# ESC-simple_V1A.net
KiCad netlist of a schematic drawn in EAGLE
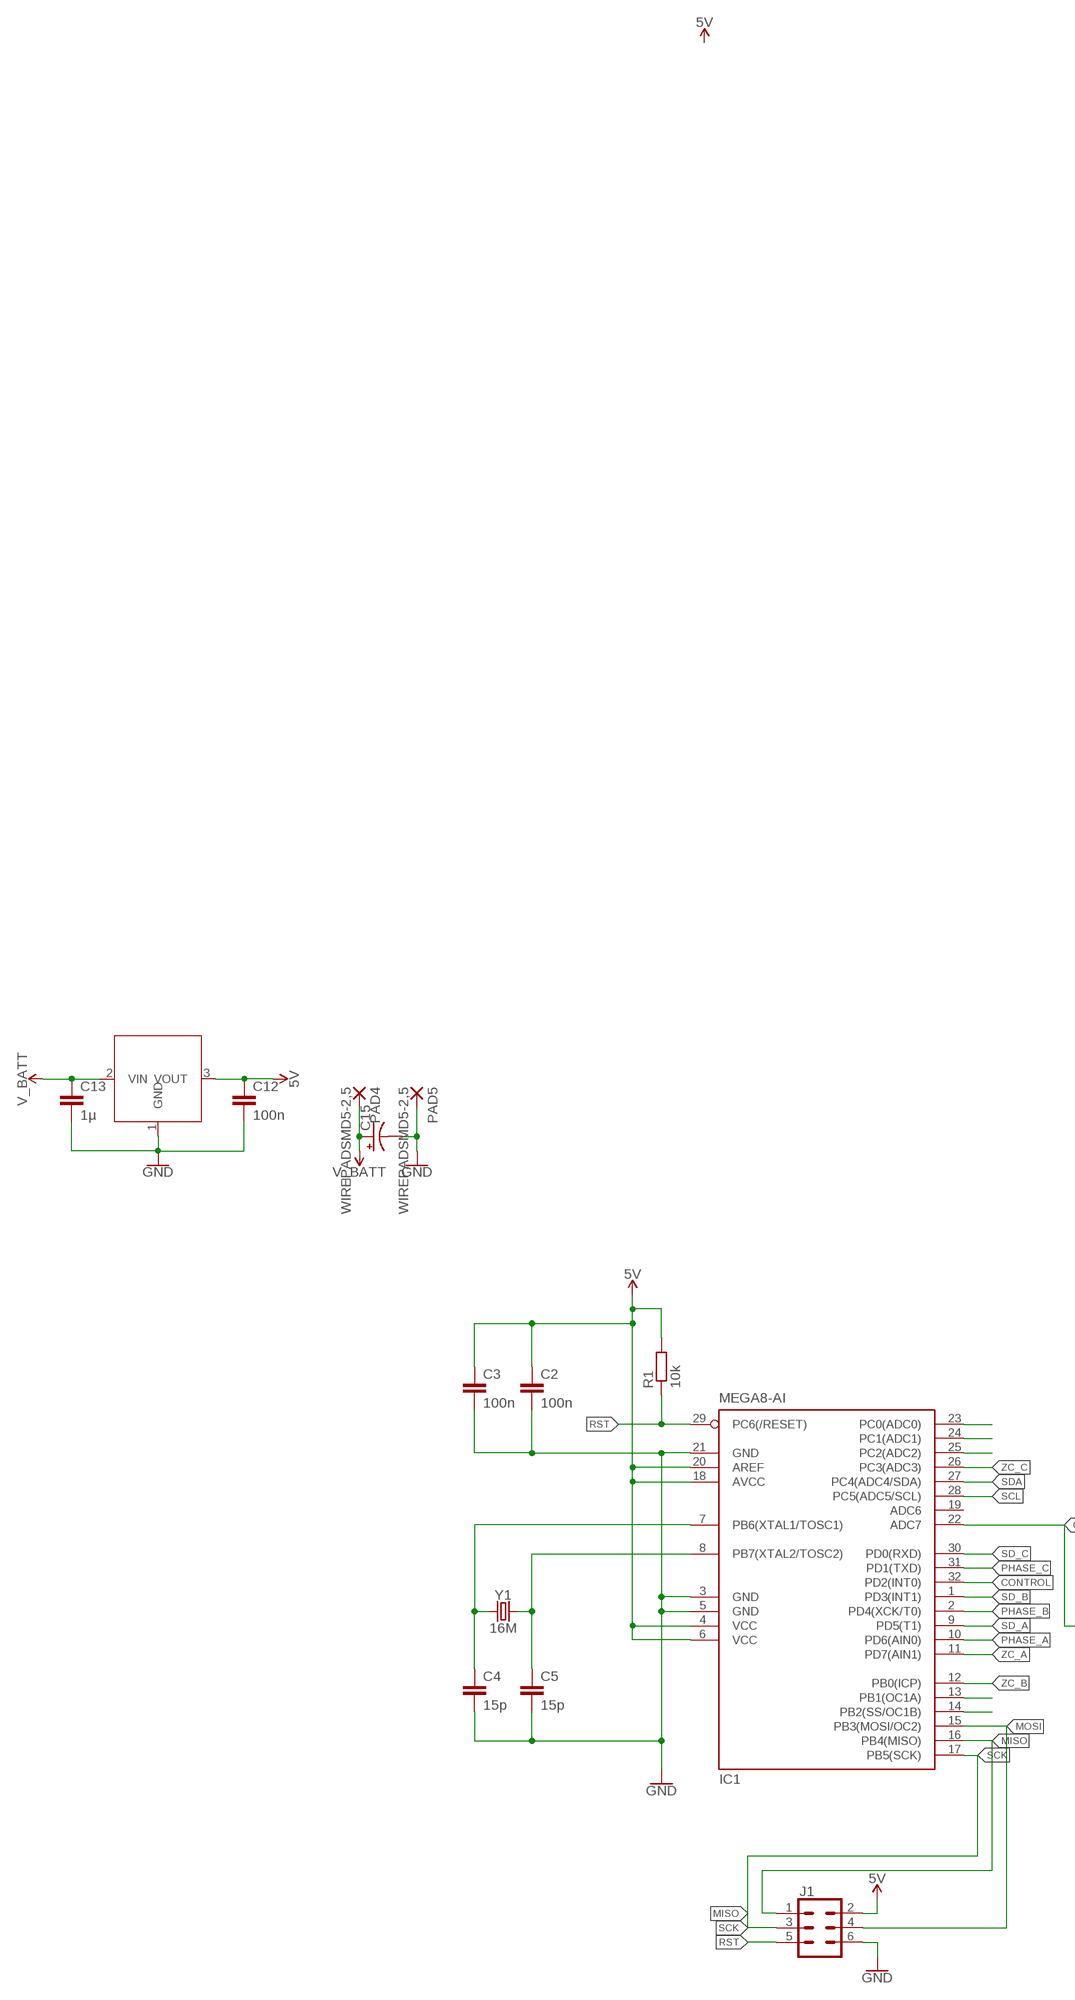
[diagram p0: schematic, sheet 1, part 1 of 2]
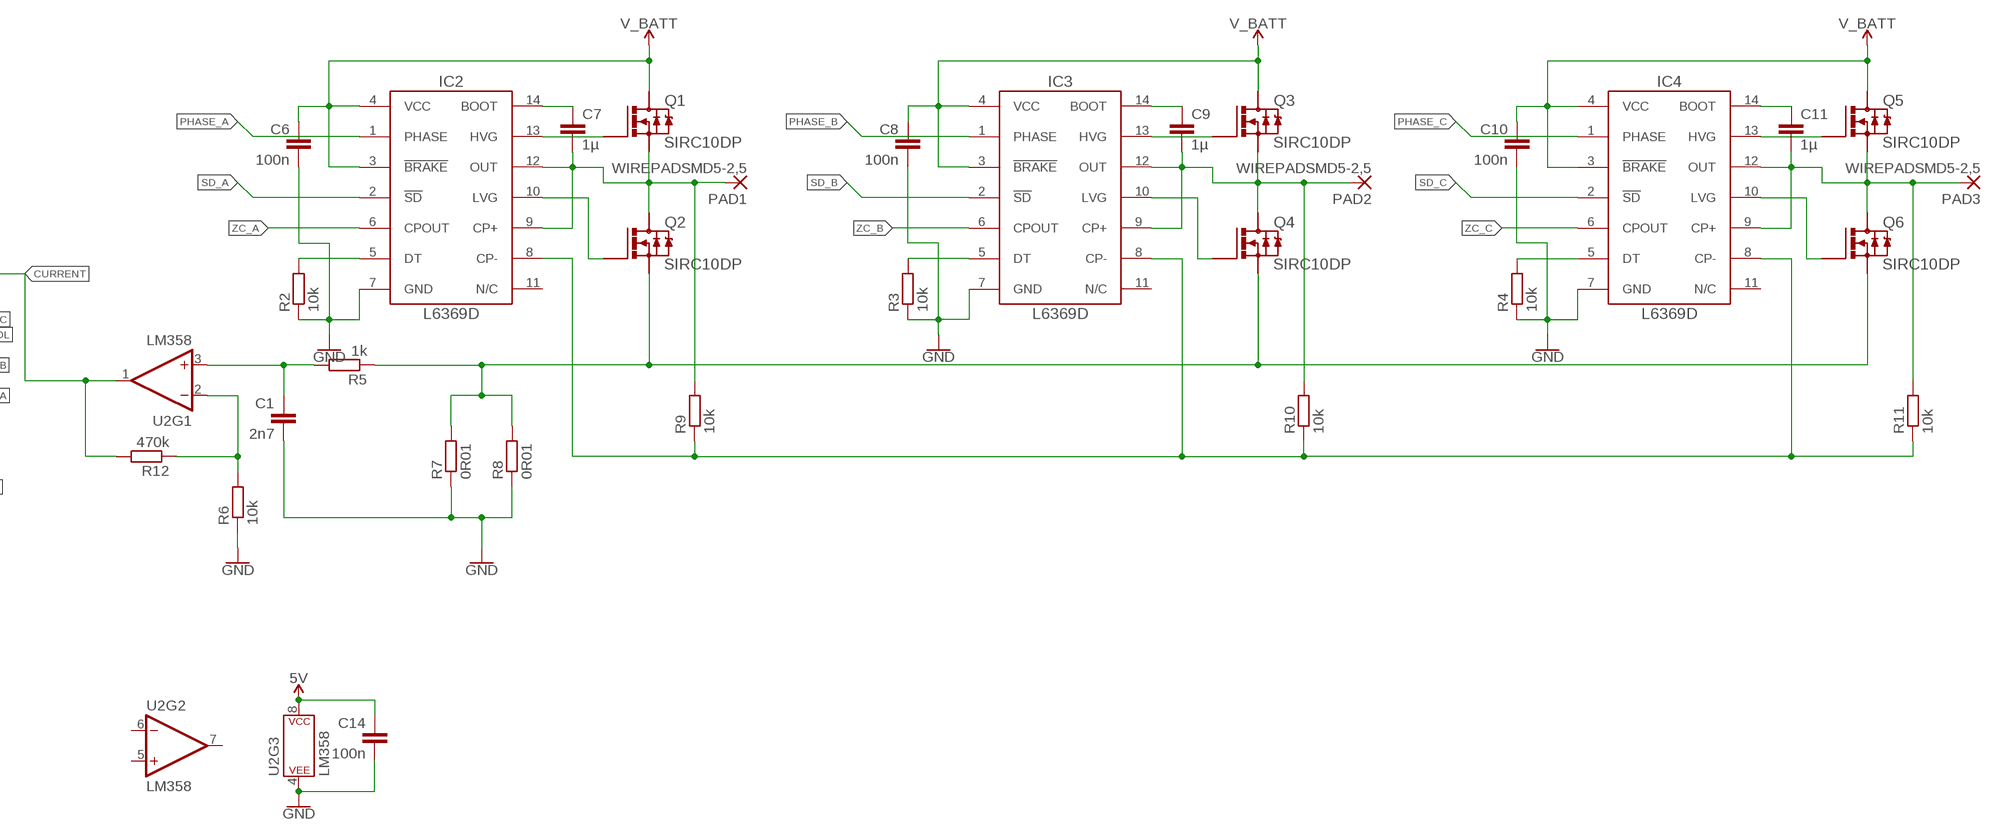
[diagram p1: schematic, sheet 1, part 2 of 2]

(export (version "E")
  (design (tool "Eeschema 10.0.6"))
  (components
    (comp (ref "C1")
      (value "2n7")
      (footprint "eagle-import:C1206K")
      (libsource (lib "eagle-import") (part "C-EUC1206K"))
    )
    (comp (ref "C2")
      (value "100n")
      (footprint "eagle-import:C1206K")
      (libsource (lib "eagle-import") (part "C-EUC1206K"))
    )
    (comp (ref "C3")
      (value "100n")
      (footprint "eagle-import:C1206K")
      (libsource (lib "eagle-import") (part "C-EUC1206K"))
    )
    (comp (ref "C4")
      (value "15p")
      (footprint "eagle-import:C1206K")
      (libsource (lib "eagle-import") (part "C-EUC1206K"))
    )
    (comp (ref "C5")
      (value "15p")
      (footprint "eagle-import:C1206K")
      (libsource (lib "eagle-import") (part "C-EUC1206K"))
    )
    (comp (ref "C6")
      (value "100n")
      (footprint "eagle-import:C1206K")
      (libsource (lib "eagle-import") (part "C-EUC1206K"))
    )
    (comp (ref "C7")
      (value "1µ")
      (footprint "eagle-import:C1206K")
      (libsource (lib "eagle-import") (part "C-EUC1206K"))
    )
    (comp (ref "C8")
      (value "100n")
      (footprint "eagle-import:C1206K")
      (libsource (lib "eagle-import") (part "C-EUC1206K"))
    )
    (comp (ref "C9")
      (value "1µ")
      (footprint "eagle-import:C1206K")
      (libsource (lib "eagle-import") (part "C-EUC1206K"))
    )
    (comp (ref "C10")
      (value "100n")
      (footprint "eagle-import:C1206K")
      (libsource (lib "eagle-import") (part "C-EUC1206K"))
    )
    (comp (ref "C11")
      (value "1µ")
      (footprint "eagle-import:C1206K")
      (libsource (lib "eagle-import") (part "C-EUC1206K"))
    )
    (comp (ref "C12")
      (value "100n")
      (footprint "eagle-import:C1206K")
      (libsource (lib "eagle-import") (part "C-EUC1206K"))
    )
    (comp (ref "C13")
      (value "1µ")
      (footprint "eagle-import:C1206K")
      (libsource (lib "eagle-import") (part "C-EUC1206K"))
    )
    (comp (ref "C14")
      (value "100n")
      (footprint "eagle-import:C1206K")
      (libsource (lib "eagle-import") (part "C-EUC1206K"))
    )
    (comp (ref "C15")
      (value "CPOL-USE5-13")
      (footprint "eagle-import:E5-13")
      (libsource (lib "eagle-import") (part "CPOL-USE5-13"))
    )
    (comp (ref "IC1")
      (value "MEGA8-AI")
      (footprint "eagle-import:TQFP32-08")
      (fields (field (name "MPN") "ATMEGA8-16AU"))
      (libsource (lib "eagle-import") (part "MEGA8-AI"))
    )
    (comp (ref "IC2")
      (value "L6369D")
      (footprint "eagle-import:SO-14")
      (libsource (lib "eagle-import") (part "L6369D"))
    )
    (comp (ref "IC3")
      (value "L6369D")
      (footprint "eagle-import:SO-14")
      (libsource (lib "eagle-import") (part "L6369D"))
    )
    (comp (ref "IC4")
      (value "L6369D")
      (footprint "eagle-import:SO-14")
      (libsource (lib "eagle-import") (part "L6369D"))
    )
    (comp (ref "J1")
      (value "CONN_03X22X3_SILK_MALE_PTH")
      (footprint "eagle-import:2X3")
      (libsource (lib "eagle-import") (part "CONN_03X22X3_SILK_MALE_PTH"))
    )
    (comp (ref "PAD1")
      (value "WIREPADSMD5-2,5")
      (footprint "eagle-import:5-2,5")
      (libsource (lib "eagle-import") (part "WIREPADSMD5-2,5"))
    )
    (comp (ref "PAD2")
      (value "WIREPADSMD5-2,5")
      (footprint "eagle-import:5-2,5")
      (libsource (lib "eagle-import") (part "WIREPADSMD5-2,5"))
    )
    (comp (ref "PAD3")
      (value "WIREPADSMD5-2,5")
      (footprint "eagle-import:5-2,5")
      (libsource (lib "eagle-import") (part "WIREPADSMD5-2,5"))
    )
    (comp (ref "PAD4")
      (value "WIREPADSMD5-2,5")
      (footprint "eagle-import:5-2,5")
      (libsource (lib "eagle-import") (part "WIREPADSMD5-2,5"))
    )
    (comp (ref "PAD5")
      (value "WIREPADSMD5-2,5")
      (footprint "eagle-import:5-2,5")
      (libsource (lib "eagle-import") (part "WIREPADSMD5-2,5"))
    )
    (comp (ref "Q1")
      (value "SIRC10DP")
      (footprint "eagle-import:POWERPAK_SO-8_SINGLE")
      (libsource (lib "eagle-import") (part "SIRC10DP"))
    )
    (comp (ref "Q2")
      (value "SIRC10DP")
      (footprint "eagle-import:POWERPAK_SO-8_SINGLE")
      (libsource (lib "eagle-import") (part "SIRC10DP"))
    )
    (comp (ref "Q3")
      (value "SIRC10DP")
      (footprint "eagle-import:POWERPAK_SO-8_SINGLE")
      (libsource (lib "eagle-import") (part "SIRC10DP"))
    )
    (comp (ref "Q4")
      (value "SIRC10DP")
      (footprint "eagle-import:POWERPAK_SO-8_SINGLE")
      (libsource (lib "eagle-import") (part "SIRC10DP"))
    )
    (comp (ref "Q5")
      (value "SIRC10DP")
      (footprint "eagle-import:POWERPAK_SO-8_SINGLE")
      (libsource (lib "eagle-import") (part "SIRC10DP"))
    )
    (comp (ref "Q6")
      (value "SIRC10DP")
      (footprint "eagle-import:POWERPAK_SO-8_SINGLE")
      (libsource (lib "eagle-import") (part "SIRC10DP"))
    )
    (comp (ref "R1")
      (value "10k")
      (footprint "eagle-import:R1206")
      (libsource (lib "eagle-import") (part "R-EU_R1206"))
    )
    (comp (ref "R2")
      (value "10k")
      (footprint "eagle-import:R1206")
      (libsource (lib "eagle-import") (part "R-EU_R1206"))
    )
    (comp (ref "R3")
      (value "10k")
      (footprint "eagle-import:R1206")
      (libsource (lib "eagle-import") (part "R-EU_R1206"))
    )
    (comp (ref "R4")
      (value "10k")
      (footprint "eagle-import:R1206")
      (libsource (lib "eagle-import") (part "R-EU_R1206"))
    )
    (comp (ref "R5")
      (value "1k")
      (footprint "eagle-import:R1206")
      (libsource (lib "eagle-import") (part "R-EU_R1206"))
    )
    (comp (ref "R6")
      (value "10k")
      (footprint "eagle-import:R1206")
      (libsource (lib "eagle-import") (part "R-EU_R1206"))
    )
    (comp (ref "R7")
      (value "0R01")
      (footprint "eagle-import:R1206")
      (libsource (lib "eagle-import") (part "R-EU_R1206"))
    )
    (comp (ref "R8")
      (value "0R01")
      (footprint "eagle-import:R1206")
      (libsource (lib "eagle-import") (part "R-EU_R1206"))
    )
    (comp (ref "R9")
      (value "10k")
      (footprint "eagle-import:R1206")
      (libsource (lib "eagle-import") (part "R-EU_R1206"))
    )
    (comp (ref "R10")
      (value "10k")
      (footprint "eagle-import:R1206")
      (libsource (lib "eagle-import") (part "R-EU_R1206"))
    )
    (comp (ref "R11")
      (value "10k")
      (footprint "eagle-import:R1206")
      (libsource (lib "eagle-import") (part "R-EU_R1206"))
    )
    (comp (ref "R12")
      (value "470k")
      (footprint "eagle-import:R1206")
      (libsource (lib "eagle-import") (part "R-EU_R1206"))
    )
    (comp (ref "U$1")
      (value "S812")
      (footprint "eagle-import:TO92L")
      (libsource (lib "eagle-import") (part "S812"))
    )
    (comp (ref "U2")
      (value "LM358")
      (footprint "eagle-import:DIP08")
      (libsource (lib "eagle-import") (part "LM358"))
    )
    (comp (ref "Y1")
      (value "16M")
      (footprint "eagle-import:HC49UP")
      (libsource (lib "eagle-import") (part "CRYSTALSMD-HC49UP"))
    )
  )
  (nets
    (net (code "1") (name "5V") (class "Default")
      (node (ref "C12") (pin "1") (pinfunction "1_1") (pintype "passive"))
      (node (ref "C14") (pin "1") (pinfunction "1_1") (pintype "passive"))
      (node (ref "C2") (pin "1") (pinfunction "1_1") (pintype "passive"))
      (node (ref "C3") (pin "1") (pinfunction "1_1") (pintype "passive"))
      (node (ref "IC1") (pin "18") (pinfunction "AVCC_18") (pintype "power_in"))
      (node (ref "IC1") (pin "20") (pinfunction "AREF_20") (pintype "passive"))
      (node (ref "IC1") (pin "4") (pinfunction "VCC_4") (pintype "power_in"))
      (node (ref "IC1") (pin "6") (pinfunction "VCC_6") (pintype "power_in"))
      (node (ref "J1") (pin "2") (pinfunction "2_2") (pintype "bidirectional"))
      (node (ref "R1") (pin "2") (pinfunction "2_2") (pintype "passive"))
      (node (ref "U$1") (pin "3") (pinfunction "VOUT_3") (pintype "power_in"))
      (node (ref "U2") (pin "8") (pinfunction "P$V+_8") (pintype "bidirectional"))
    )
    (net (code "2") (name "CONTROL") (class "Default")
      (node (ref "IC1") (pin "32") (pinfunction "PD2(INT0)_32") (pintype "bidirectional"))
    )
    (net (code "3") (name "CURRENT") (class "Default")
      (node (ref "IC1") (pin "22") (pinfunction "ADC7_22") (pintype "bidirectional"))
      (node (ref "R12") (pin "2") (pinfunction "2_2") (pintype "passive"))
      (node (ref "U2") (pin "1") (pinfunction "OUT_1") (pintype "output"))
    )
    (net (code "4") (name "GND") (class "Default")
      (node (ref "C1") (pin "2") (pinfunction "2_2") (pintype "passive"))
      (node (ref "C10") (pin "2") (pinfunction "2_2") (pintype "passive"))
      (node (ref "C12") (pin "2") (pinfunction "2_2") (pintype "passive"))
      (node (ref "C13") (pin "2") (pinfunction "2_2") (pintype "passive"))
      (node (ref "C14") (pin "2") (pinfunction "2_2") (pintype "passive"))
      (node (ref "C15") (pin "-") (pinfunction "-_-") (pintype "passive"))
      (node (ref "C2") (pin "2") (pinfunction "2_2") (pintype "passive"))
      (node (ref "C3") (pin "2") (pinfunction "2_2") (pintype "passive"))
      (node (ref "C4") (pin "2") (pinfunction "2_2") (pintype "passive"))
      (node (ref "C5") (pin "2") (pinfunction "2_2") (pintype "passive"))
      (node (ref "C6") (pin "2") (pinfunction "2_2") (pintype "passive"))
      (node (ref "C8") (pin "2") (pinfunction "2_2") (pintype "passive"))
      (node (ref "IC1") (pin "21") (pinfunction "GND_21") (pintype "power_in"))
      (node (ref "IC1") (pin "3") (pinfunction "GND_3") (pintype "power_in"))
      (node (ref "IC1") (pin "5") (pinfunction "GND_5") (pintype "power_in"))
      (node (ref "IC2") (pin "7") (pinfunction "GND_7") (pintype "power_in"))
      (node (ref "IC3") (pin "7") (pinfunction "GND_7") (pintype "power_in"))
      (node (ref "IC4") (pin "7") (pinfunction "GND_7") (pintype "power_in"))
      (node (ref "J1") (pin "6") (pinfunction "6_6") (pintype "bidirectional"))
      (node (ref "PAD5") (pin "1") (pinfunction "P_1") (pintype "passive"))
      (node (ref "R2") (pin "1") (pinfunction "1_1") (pintype "passive"))
      (node (ref "R3") (pin "1") (pinfunction "1_1") (pintype "passive"))
      (node (ref "R4") (pin "1") (pinfunction "1_1") (pintype "passive"))
      (node (ref "R6") (pin "1") (pinfunction "1_1") (pintype "passive"))
      (node (ref "R7") (pin "1") (pinfunction "1_1") (pintype "passive"))
      (node (ref "R8") (pin "1") (pinfunction "1_1") (pintype "passive"))
      (node (ref "U$1") (pin "1") (pinfunction "GND_1") (pintype "power_in"))
      (node (ref "U2") (pin "4") (pinfunction "P$V-_4") (pintype "bidirectional"))
    )
    (net (code "5") (name "MISO") (class "Default")
      (node (ref "IC1") (pin "16") (pinfunction "PB4(MISO)_16") (pintype "bidirectional"))
      (node (ref "J1") (pin "1") (pinfunction "1_1") (pintype "bidirectional"))
    )
    (net (code "6") (name "MOSI") (class "Default")
      (node (ref "IC1") (pin "15") (pinfunction "PB3(MOSI/OC2)_15") (pintype "bidirectional"))
      (node (ref "J1") (pin "4") (pinfunction "4_4") (pintype "bidirectional"))
    )
    (net (code "7") (name "Net-(IC1-PB6(XTAL1{slash}TOSC1))") (class "Default")
      (node (ref "C4") (pin "1") (pinfunction "1_1") (pintype "passive"))
      (node (ref "IC1") (pin "7") (pinfunction "PB6(XTAL1/TOSC1)_7") (pintype "bidirectional"))
      (node (ref "Y1") (pin "1") (pinfunction "1_1") (pintype "passive"))
    )
    (net (code "8") (name "Net-(IC1-PB7(XTAL2{slash}TOSC2))") (class "Default")
      (node (ref "C5") (pin "1") (pinfunction "1_1") (pintype "passive"))
      (node (ref "IC1") (pin "8") (pinfunction "PB7(XTAL2/TOSC2)_8") (pintype "bidirectional"))
      (node (ref "Y1") (pin "2") (pinfunction "2_2") (pintype "passive"))
    )
    (net (code "9") (name "Net-(IC2-BOOT)") (class "Default")
      (node (ref "C7") (pin "1") (pinfunction "1_1") (pintype "passive"))
      (node (ref "IC2") (pin "14") (pinfunction "BOOT_14") (pintype "power_in"))
    )
    (net (code "10") (name "Net-(IC2-CP+)") (class "Default")
      (node (ref "C7") (pin "2") (pinfunction "2_2") (pintype "passive"))
      (node (ref "IC2") (pin "12") (pinfunction "OUT_12") (pintype "output"))
      (node (ref "IC2") (pin "9") (pinfunction "CP+_9") (pintype "input"))
      (node (ref "PAD1") (pin "1") (pinfunction "P_1") (pintype "passive"))
      (node (ref "Q1") (pin "1") (pinfunction "S_1") (pintype "bidirectional"))
      (node (ref "Q1") (pin "2") (pinfunction "S_2") (pintype "bidirectional"))
      (node (ref "Q1") (pin "3") (pinfunction "S_3") (pintype "bidirectional"))
      (node (ref "Q2") (pin "5") (pinfunction "D_5") (pintype "bidirectional"))
      (node (ref "Q2") (pin "6") (pinfunction "D_6") (pintype "bidirectional"))
      (node (ref "Q2") (pin "7") (pinfunction "D_7") (pintype "bidirectional"))
      (node (ref "Q2") (pin "8") (pinfunction "D_8") (pintype "bidirectional"))
      (node (ref "Q2") (pin "9") (pinfunction "D_9") (pintype "bidirectional"))
      (node (ref "R9") (pin "2") (pinfunction "2_2") (pintype "passive"))
    )
    (net (code "11") (name "Net-(IC2-CP-)") (class "Default")
      (node (ref "IC2") (pin "8") (pinfunction "CP-_8") (pintype "input"))
      (node (ref "IC3") (pin "8") (pinfunction "CP-_8") (pintype "input"))
      (node (ref "IC4") (pin "8") (pinfunction "CP-_8") (pintype "input"))
      (node (ref "R10") (pin "1") (pinfunction "1_1") (pintype "passive"))
      (node (ref "R11") (pin "1") (pinfunction "1_1") (pintype "passive"))
      (node (ref "R9") (pin "1") (pinfunction "1_1") (pintype "passive"))
    )
    (net (code "12") (name "Net-(IC2-DT)") (class "Default")
      (node (ref "IC2") (pin "5") (pinfunction "DT_5") (pintype "input"))
      (node (ref "R2") (pin "2") (pinfunction "2_2") (pintype "passive"))
    )
    (net (code "13") (name "Net-(IC2-HVG)") (class "Default")
      (node (ref "IC2") (pin "13") (pinfunction "HVG_13") (pintype "output"))
      (node (ref "Q1") (pin "4") (pinfunction "G_4") (pintype "bidirectional"))
    )
    (net (code "14") (name "Net-(IC2-LVG)") (class "Default")
      (node (ref "IC2") (pin "10") (pinfunction "LVG_10") (pintype "output"))
      (node (ref "Q2") (pin "4") (pinfunction "G_4") (pintype "bidirectional"))
    )
    (net (code "15") (name "Net-(IC3-BOOT)") (class "Default")
      (node (ref "C9") (pin "1") (pinfunction "1_1") (pintype "passive"))
      (node (ref "IC3") (pin "14") (pinfunction "BOOT_14") (pintype "power_in"))
    )
    (net (code "16") (name "Net-(IC3-CP+)") (class "Default")
      (node (ref "C9") (pin "2") (pinfunction "2_2") (pintype "passive"))
      (node (ref "IC3") (pin "12") (pinfunction "OUT_12") (pintype "output"))
      (node (ref "IC3") (pin "9") (pinfunction "CP+_9") (pintype "input"))
      (node (ref "PAD2") (pin "1") (pinfunction "P_1") (pintype "passive"))
      (node (ref "Q3") (pin "1") (pinfunction "S_1") (pintype "bidirectional"))
      (node (ref "Q3") (pin "2") (pinfunction "S_2") (pintype "bidirectional"))
      (node (ref "Q3") (pin "3") (pinfunction "S_3") (pintype "bidirectional"))
      (node (ref "Q4") (pin "5") (pinfunction "D_5") (pintype "bidirectional"))
      (node (ref "Q4") (pin "6") (pinfunction "D_6") (pintype "bidirectional"))
      (node (ref "Q4") (pin "7") (pinfunction "D_7") (pintype "bidirectional"))
      (node (ref "Q4") (pin "8") (pinfunction "D_8") (pintype "bidirectional"))
      (node (ref "Q4") (pin "9") (pinfunction "D_9") (pintype "bidirectional"))
      (node (ref "R10") (pin "2") (pinfunction "2_2") (pintype "passive"))
    )
    (net (code "17") (name "Net-(IC3-DT)") (class "Default")
      (node (ref "IC3") (pin "5") (pinfunction "DT_5") (pintype "input"))
      (node (ref "R3") (pin "2") (pinfunction "2_2") (pintype "passive"))
    )
    (net (code "18") (name "Net-(IC3-HVG)") (class "Default")
      (node (ref "IC3") (pin "13") (pinfunction "HVG_13") (pintype "output"))
      (node (ref "Q3") (pin "4") (pinfunction "G_4") (pintype "bidirectional"))
    )
    (net (code "19") (name "Net-(IC3-LVG)") (class "Default")
      (node (ref "IC3") (pin "10") (pinfunction "LVG_10") (pintype "output"))
      (node (ref "Q4") (pin "4") (pinfunction "G_4") (pintype "bidirectional"))
    )
    (net (code "20") (name "Net-(IC4-BOOT)") (class "Default")
      (node (ref "C11") (pin "1") (pinfunction "1_1") (pintype "passive"))
      (node (ref "IC4") (pin "14") (pinfunction "BOOT_14") (pintype "power_in"))
    )
    (net (code "21") (name "Net-(IC4-CP+)") (class "Default")
      (node (ref "C11") (pin "2") (pinfunction "2_2") (pintype "passive"))
      (node (ref "IC4") (pin "12") (pinfunction "OUT_12") (pintype "output"))
      (node (ref "IC4") (pin "9") (pinfunction "CP+_9") (pintype "input"))
      (node (ref "PAD3") (pin "1") (pinfunction "P_1") (pintype "passive"))
      (node (ref "Q5") (pin "1") (pinfunction "S_1") (pintype "bidirectional"))
      (node (ref "Q5") (pin "2") (pinfunction "S_2") (pintype "bidirectional"))
      (node (ref "Q5") (pin "3") (pinfunction "S_3") (pintype "bidirectional"))
      (node (ref "Q6") (pin "5") (pinfunction "D_5") (pintype "bidirectional"))
      (node (ref "Q6") (pin "6") (pinfunction "D_6") (pintype "bidirectional"))
      (node (ref "Q6") (pin "7") (pinfunction "D_7") (pintype "bidirectional"))
      (node (ref "Q6") (pin "8") (pinfunction "D_8") (pintype "bidirectional"))
      (node (ref "Q6") (pin "9") (pinfunction "D_9") (pintype "bidirectional"))
      (node (ref "R11") (pin "2") (pinfunction "2_2") (pintype "passive"))
    )
    (net (code "22") (name "Net-(IC4-DT)") (class "Default")
      (node (ref "IC4") (pin "5") (pinfunction "DT_5") (pintype "input"))
      (node (ref "R4") (pin "2") (pinfunction "2_2") (pintype "passive"))
    )
    (net (code "23") (name "Net-(IC4-HVG)") (class "Default")
      (node (ref "IC4") (pin "13") (pinfunction "HVG_13") (pintype "output"))
      (node (ref "Q5") (pin "4") (pinfunction "G_4") (pintype "bidirectional"))
    )
    (net (code "24") (name "Net-(IC4-LVG)") (class "Default")
      (node (ref "IC4") (pin "10") (pinfunction "LVG_10") (pintype "output"))
      (node (ref "Q6") (pin "4") (pinfunction "G_4") (pintype "bidirectional"))
    )
    (net (code "25") (name "Net-(Q2-S-Pad1)") (class "Default")
      (node (ref "Q2") (pin "1") (pinfunction "S_1") (pintype "bidirectional"))
      (node (ref "Q2") (pin "2") (pinfunction "S_2") (pintype "bidirectional"))
      (node (ref "Q2") (pin "3") (pinfunction "S_3") (pintype "bidirectional"))
      (node (ref "Q4") (pin "1") (pinfunction "S_1") (pintype "bidirectional"))
      (node (ref "Q4") (pin "2") (pinfunction "S_2") (pintype "bidirectional"))
      (node (ref "Q4") (pin "3") (pinfunction "S_3") (pintype "bidirectional"))
      (node (ref "Q6") (pin "1") (pinfunction "S_1") (pintype "bidirectional"))
      (node (ref "Q6") (pin "2") (pinfunction "S_2") (pintype "bidirectional"))
      (node (ref "Q6") (pin "3") (pinfunction "S_3") (pintype "bidirectional"))
      (node (ref "R5") (pin "1") (pinfunction "1_1") (pintype "passive"))
      (node (ref "R7") (pin "2") (pinfunction "2_2") (pintype "passive"))
      (node (ref "R8") (pin "2") (pinfunction "2_2") (pintype "passive"))
    )
    (net (code "26") (name "Net-(U2A-+IN)") (class "Default")
      (node (ref "C1") (pin "1") (pinfunction "1_1") (pintype "passive"))
      (node (ref "R5") (pin "2") (pinfunction "2_2") (pintype "passive"))
      (node (ref "U2") (pin "3") (pinfunction "+IN_3") (pintype "input"))
    )
    (net (code "27") (name "Net-(U2A--IN)") (class "Default")
      (node (ref "R12") (pin "1") (pinfunction "1_1") (pintype "passive"))
      (node (ref "R6") (pin "2") (pinfunction "2_2") (pintype "passive"))
      (node (ref "U2") (pin "2") (pinfunction "-IN_2") (pintype "input"))
    )
    (net (code "28") (name "PHASE_A") (class "Default")
      (node (ref "IC1") (pin "10") (pinfunction "PD6(AIN0)_10") (pintype "bidirectional"))
      (node (ref "IC2") (pin "1") (pinfunction "PHASE_1") (pintype "input"))
    )
    (net (code "29") (name "PHASE_B") (class "Default")
      (node (ref "IC1") (pin "2") (pinfunction "PD4(XCK/T0)_2") (pintype "bidirectional"))
      (node (ref "IC3") (pin "1") (pinfunction "PHASE_1") (pintype "input"))
    )
    (net (code "30") (name "PHASE_C") (class "Default")
      (node (ref "IC1") (pin "31") (pinfunction "PD1(TXD)_31") (pintype "bidirectional"))
      (node (ref "IC4") (pin "1") (pinfunction "PHASE_1") (pintype "input"))
    )
    (net (code "31") (name "RST") (class "Default")
      (node (ref "IC1") (pin "29") (pinfunction "PC6(/RESET)_29") (pintype "bidirectional"))
      (node (ref "J1") (pin "5") (pinfunction "5_5") (pintype "bidirectional"))
      (node (ref "R1") (pin "1") (pinfunction "1_1") (pintype "passive"))
    )
    (net (code "32") (name "SCK") (class "Default")
      (node (ref "IC1") (pin "17") (pinfunction "PB5(SCK)_17") (pintype "bidirectional"))
      (node (ref "J1") (pin "3") (pinfunction "3_3") (pintype "bidirectional"))
    )
    (net (code "33") (name "SCL") (class "Default")
      (node (ref "IC1") (pin "28") (pinfunction "PC5(ADC5/SCL)_28") (pintype "bidirectional"))
    )
    (net (code "34") (name "SDA") (class "Default")
      (node (ref "IC1") (pin "27") (pinfunction "PC4(ADC4/SDA)_27") (pintype "bidirectional"))
    )
    (net (code "35") (name "SD_A") (class "Default")
      (node (ref "IC1") (pin "9") (pinfunction "PD5(T1)_9") (pintype "bidirectional"))
      (node (ref "IC2") (pin "2") (pinfunction "~{SD}_2") (pintype "input"))
    )
    (net (code "36") (name "SD_B") (class "Default")
      (node (ref "IC1") (pin "1") (pinfunction "PD3(INT1)_1") (pintype "bidirectional"))
      (node (ref "IC3") (pin "2") (pinfunction "~{SD}_2") (pintype "input"))
    )
    (net (code "37") (name "SD_C") (class "Default")
      (node (ref "IC1") (pin "30") (pinfunction "PD0(RXD)_30") (pintype "bidirectional"))
      (node (ref "IC4") (pin "2") (pinfunction "~{SD}_2") (pintype "input"))
    )
    (net (code "38") (name "V_BATT") (class "Default")
      (node (ref "C10") (pin "1") (pinfunction "1_1") (pintype "passive"))
      (node (ref "C13") (pin "1") (pinfunction "1_1") (pintype "passive"))
      (node (ref "C15") (pin "+") (pinfunction "+_+") (pintype "passive"))
      (node (ref "C6") (pin "1") (pinfunction "1_1") (pintype "passive"))
      (node (ref "C8") (pin "1") (pinfunction "1_1") (pintype "passive"))
      (node (ref "IC2") (pin "3") (pinfunction "~{BRAKE}_3") (pintype "input"))
      (node (ref "IC2") (pin "4") (pinfunction "VCC_4") (pintype "power_in"))
      (node (ref "IC3") (pin "3") (pinfunction "~{BRAKE}_3") (pintype "input"))
      (node (ref "IC3") (pin "4") (pinfunction "VCC_4") (pintype "power_in"))
      (node (ref "IC4") (pin "3") (pinfunction "~{BRAKE}_3") (pintype "input"))
      (node (ref "IC4") (pin "4") (pinfunction "VCC_4") (pintype "power_in"))
      (node (ref "PAD4") (pin "1") (pinfunction "P_1") (pintype "passive"))
      (node (ref "Q1") (pin "5") (pinfunction "D_5") (pintype "bidirectional"))
      (node (ref "Q1") (pin "6") (pinfunction "D_6") (pintype "bidirectional"))
      (node (ref "Q1") (pin "7") (pinfunction "D_7") (pintype "bidirectional"))
      (node (ref "Q1") (pin "8") (pinfunction "D_8") (pintype "bidirectional"))
      (node (ref "Q1") (pin "9") (pinfunction "D_9") (pintype "bidirectional"))
      (node (ref "Q3") (pin "5") (pinfunction "D_5") (pintype "bidirectional"))
      (node (ref "Q3") (pin "6") (pinfunction "D_6") (pintype "bidirectional"))
      (node (ref "Q3") (pin "7") (pinfunction "D_7") (pintype "bidirectional"))
      (node (ref "Q3") (pin "8") (pinfunction "D_8") (pintype "bidirectional"))
      (node (ref "Q3") (pin "9") (pinfunction "D_9") (pintype "bidirectional"))
      (node (ref "Q5") (pin "5") (pinfunction "D_5") (pintype "bidirectional"))
      (node (ref "Q5") (pin "6") (pinfunction "D_6") (pintype "bidirectional"))
      (node (ref "Q5") (pin "7") (pinfunction "D_7") (pintype "bidirectional"))
      (node (ref "Q5") (pin "8") (pinfunction "D_8") (pintype "bidirectional"))
      (node (ref "Q5") (pin "9") (pinfunction "D_9") (pintype "bidirectional"))
      (node (ref "U$1") (pin "2") (pinfunction "VIN_2") (pintype "power_in"))
    )
    (net (code "39") (name "ZC_A") (class "Default")
      (node (ref "IC1") (pin "11") (pinfunction "PD7(AIN1)_11") (pintype "bidirectional"))
      (node (ref "IC2") (pin "6") (pinfunction "CPOUT_6") (pintype "output"))
    )
    (net (code "40") (name "ZC_B") (class "Default")
      (node (ref "IC1") (pin "12") (pinfunction "PB0(ICP)_12") (pintype "bidirectional"))
      (node (ref "IC3") (pin "6") (pinfunction "CPOUT_6") (pintype "output"))
    )
    (net (code "41") (name "ZC_C") (class "Default")
      (node (ref "IC1") (pin "26") (pinfunction "PC3(ADC3)_26") (pintype "bidirectional"))
      (node (ref "IC4") (pin "6") (pinfunction "CPOUT_6") (pintype "output"))
    )
    (net (code "42") (name "unconnected-(IC1-ADC6-Pad19)") (class "Default")
      (node (ref "IC1") (pin "19") (pinfunction "ADC6_19") (pintype "bidirectional"))
    )
    (net (code "43") (name "unconnected-(IC1-PB1(OC1A)-Pad13)") (class "Default")
      (node (ref "IC1") (pin "13") (pinfunction "PB1(OC1A)_13") (pintype "bidirectional"))
    )
    (net (code "44") (name "unconnected-(IC1-PB2(SS{slash}OC1B)-Pad14)") (class "Default")
      (node (ref "IC1") (pin "14") (pinfunction "PB2(SS/OC1B)_14") (pintype "bidirectional"))
    )
    (net (code "45") (name "unconnected-(IC1-PC0(ADC0)-Pad23)") (class "Default")
      (node (ref "IC1") (pin "23") (pinfunction "PC0(ADC0)_23") (pintype "bidirectional"))
    )
    (net (code "46") (name "unconnected-(IC1-PC1(ADC1)-Pad24)") (class "Default")
      (node (ref "IC1") (pin "24") (pinfunction "PC1(ADC1)_24") (pintype "bidirectional"))
    )
    (net (code "47") (name "unconnected-(IC1-PC2(ADC2)-Pad25)") (class "Default")
      (node (ref "IC1") (pin "25") (pinfunction "PC2(ADC2)_25") (pintype "bidirectional"))
    )
    (net (code "48") (name "unconnected-(IC2-N{slash}C-Pad11)") (class "Default")
      (node (ref "IC2") (pin "11") (pinfunction "N/C_11") (pintype "no_connect"))
    )
    (net (code "49") (name "unconnected-(IC3-N{slash}C-Pad11)") (class "Default")
      (node (ref "IC3") (pin "11") (pinfunction "N/C_11") (pintype "no_connect"))
    )
    (net (code "50") (name "unconnected-(IC4-N{slash}C-Pad11)") (class "Default")
      (node (ref "IC4") (pin "11") (pinfunction "N/C_11") (pintype "no_connect"))
    )
    (net (code "51") (name "unconnected-(U2B-+IN-Pad5)") (class "Default")
      (node (ref "U2") (pin "5") (pinfunction "+IN_5") (pintype "input"))
    )
    (net (code "52") (name "unconnected-(U2B--IN-Pad6)") (class "Default")
      (node (ref "U2") (pin "6") (pinfunction "-IN_6") (pintype "input"))
    )
    (net (code "53") (name "unconnected-(U2B-OUT-Pad7)") (class "Default")
      (node (ref "U2") (pin "7") (pinfunction "OUT_7") (pintype "output"))
    )
  )
)
